# WORD_BYTE_1.net
KiCad netlist of a schematic drawn in EAGLE
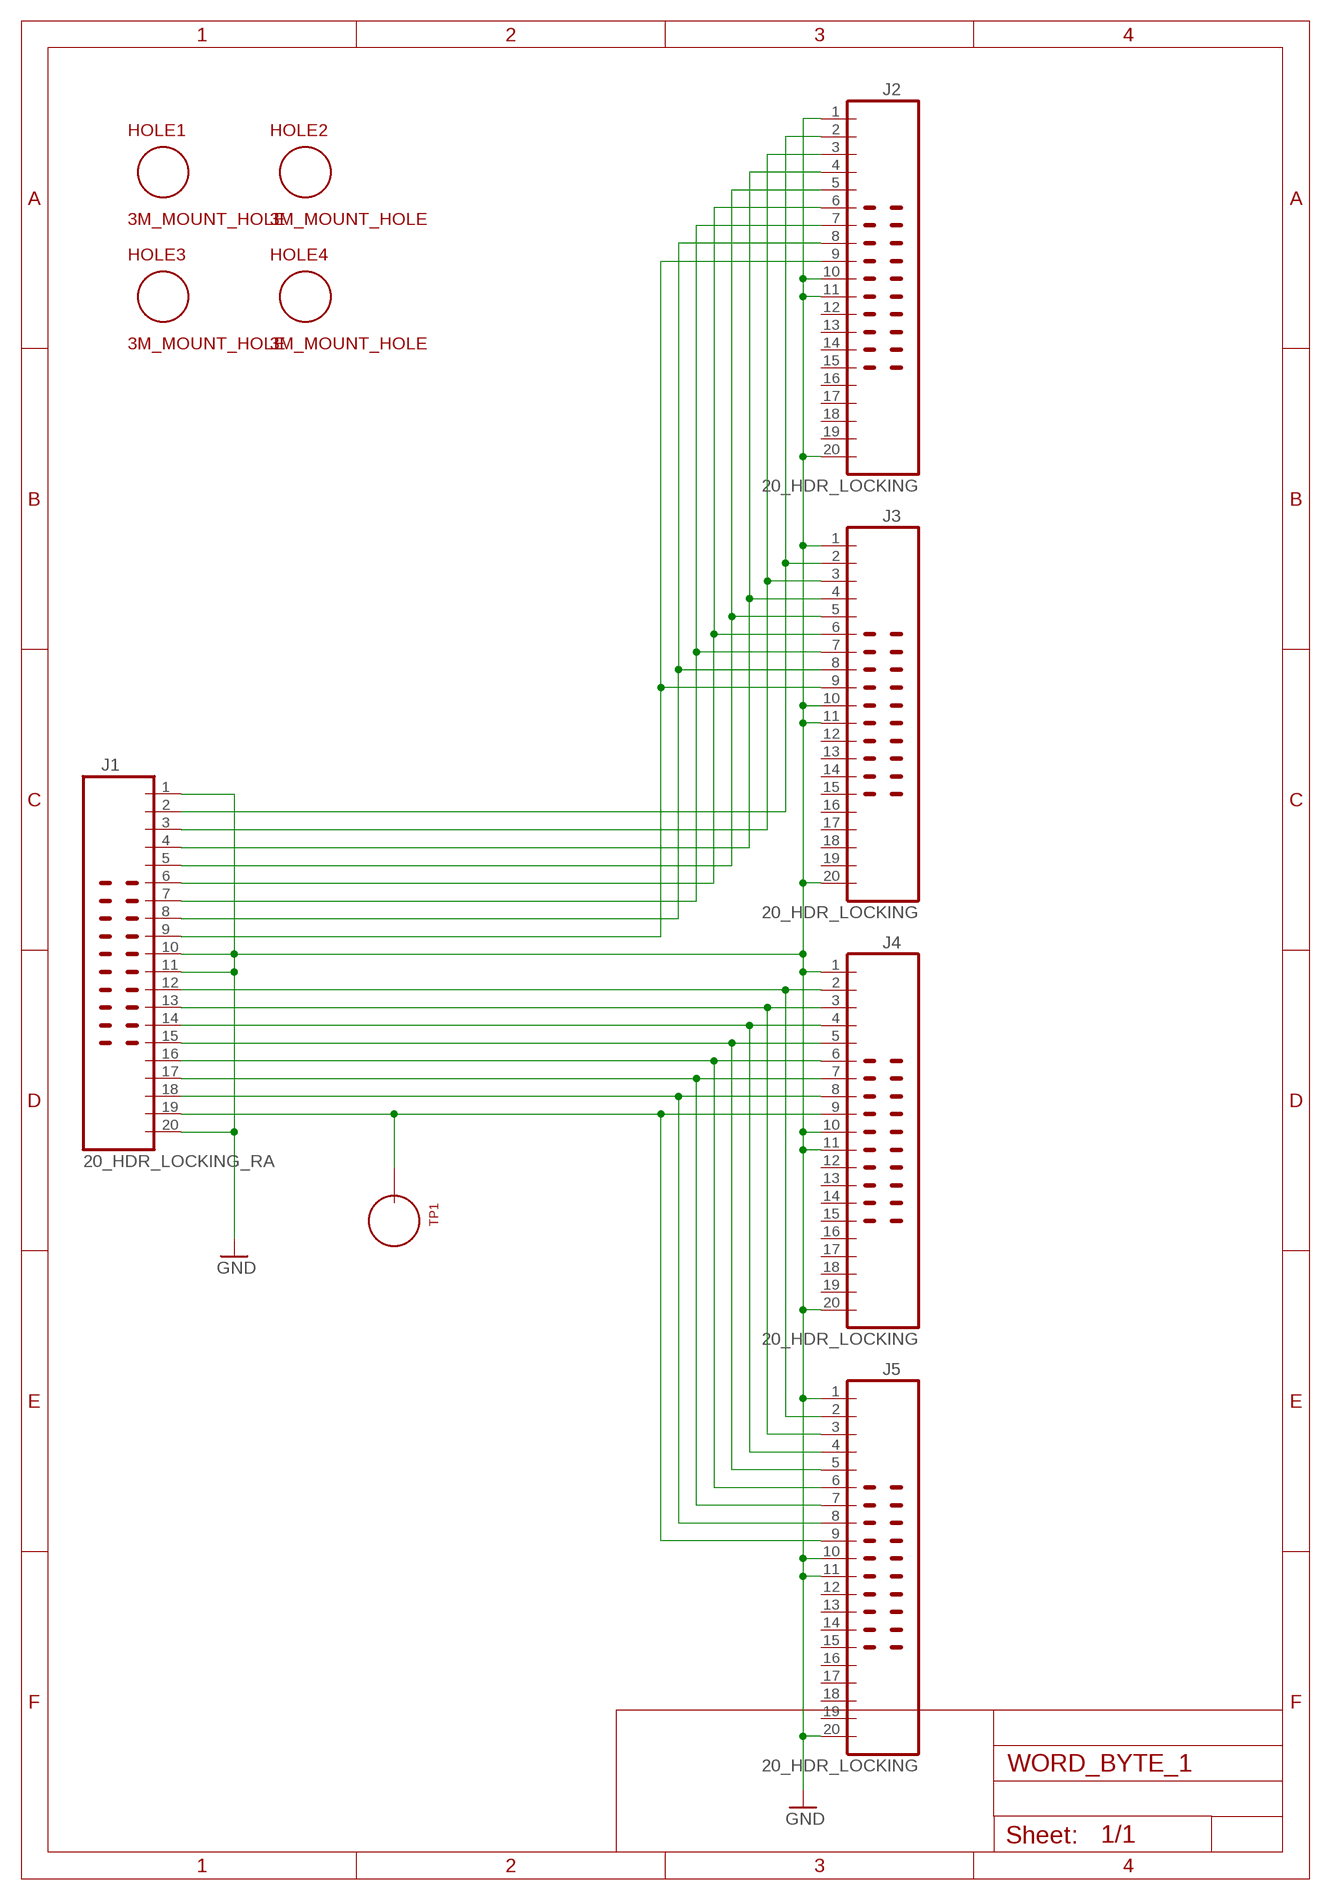
[diagram p0: schematic, sheet 1]

(export (version "E")
  (design (tool "Eeschema 10.0.6"))
  (components
    (comp (ref "HOLE1")
      (value "3M_MOUNT_HOLE")
      (footprint "eagle-import:3M_HOLE")
      (libsource (lib "eagle-import") (part "3M_MOUNT_HOLE"))
    )
    (comp (ref "HOLE2")
      (value "3M_MOUNT_HOLE")
      (footprint "eagle-import:3M_HOLE")
      (libsource (lib "eagle-import") (part "3M_MOUNT_HOLE"))
    )
    (comp (ref "HOLE3")
      (value "3M_MOUNT_HOLE")
      (footprint "eagle-import:3M_HOLE")
      (libsource (lib "eagle-import") (part "3M_MOUNT_HOLE"))
    )
    (comp (ref "HOLE4")
      (value "3M_MOUNT_HOLE")
      (footprint "eagle-import:3M_HOLE")
      (libsource (lib "eagle-import") (part "3M_MOUNT_HOLE"))
    )
    (comp (ref "J1")
      (value "20_HDR_LOCKING_RA")
      (footprint "eagle-import:20_HDR_LOCKING_RA")
      (libsource (lib "eagle-import") (part "20_HDR_LOCKING_RA"))
    )
    (comp (ref "J2")
      (value "20_HDR_LOCKING")
      (footprint "eagle-import:20_HDR_LOCKING")
      (libsource (lib "eagle-import") (part "20_HDR_LOCKING"))
    )
    (comp (ref "J3")
      (value "20_HDR_LOCKING")
      (footprint "eagle-import:20_HDR_LOCKING")
      (libsource (lib "eagle-import") (part "20_HDR_LOCKING"))
    )
    (comp (ref "J4")
      (value "20_HDR_LOCKING")
      (footprint "eagle-import:20_HDR_LOCKING")
      (libsource (lib "eagle-import") (part "20_HDR_LOCKING"))
    )
    (comp (ref "J5")
      (value "20_HDR_LOCKING")
      (footprint "eagle-import:20_HDR_LOCKING")
      (libsource (lib "eagle-import") (part "20_HDR_LOCKING"))
    )
    (comp (ref "TP1")
      (value "TEST_LOOP")
      (footprint "eagle-import:TEST_LOOP")
      (libsource (lib "eagle-import") (part "TEST_LOOP"))
    )
  )
  (nets
    (net (code "1") (name "GND") (class "Default")
      (node (ref "J1") (pin "1") (pinfunction "1_1") (pintype "bidirectional"))
      (node (ref "J1") (pin "10") (pinfunction "10_10") (pintype "bidirectional"))
      (node (ref "J1") (pin "11") (pinfunction "11_11") (pintype "bidirectional"))
      (node (ref "J1") (pin "20") (pinfunction "20_20") (pintype "bidirectional"))
      (node (ref "J2") (pin "1") (pinfunction "1_1") (pintype "bidirectional"))
      (node (ref "J2") (pin "10") (pinfunction "10_10") (pintype "bidirectional"))
      (node (ref "J2") (pin "11") (pinfunction "11_11") (pintype "bidirectional"))
      (node (ref "J2") (pin "20") (pinfunction "20_20") (pintype "bidirectional"))
      (node (ref "J3") (pin "1") (pinfunction "1_1") (pintype "bidirectional"))
      (node (ref "J3") (pin "10") (pinfunction "10_10") (pintype "bidirectional"))
      (node (ref "J3") (pin "11") (pinfunction "11_11") (pintype "bidirectional"))
      (node (ref "J3") (pin "20") (pinfunction "20_20") (pintype "bidirectional"))
      (node (ref "J4") (pin "1") (pinfunction "1_1") (pintype "bidirectional"))
      (node (ref "J4") (pin "10") (pinfunction "10_10") (pintype "bidirectional"))
      (node (ref "J4") (pin "11") (pinfunction "11_11") (pintype "bidirectional"))
      (node (ref "J4") (pin "20") (pinfunction "20_20") (pintype "bidirectional"))
      (node (ref "J5") (pin "1") (pinfunction "1_1") (pintype "bidirectional"))
      (node (ref "J5") (pin "10") (pinfunction "10_10") (pintype "bidirectional"))
      (node (ref "J5") (pin "11") (pinfunction "11_11") (pintype "bidirectional"))
      (node (ref "J5") (pin "20") (pinfunction "20_20") (pintype "bidirectional"))
    )
    (net (code "2") (name "Net-(J1-Pad2)") (class "Default")
      (node (ref "J1") (pin "2") (pinfunction "2_2") (pintype "bidirectional"))
      (node (ref "J2") (pin "2") (pinfunction "2_2") (pintype "bidirectional"))
      (node (ref "J3") (pin "2") (pinfunction "2_2") (pintype "bidirectional"))
    )
    (net (code "3") (name "Net-(J1-Pad3)") (class "Default")
      (node (ref "J1") (pin "3") (pinfunction "3_3") (pintype "bidirectional"))
      (node (ref "J2") (pin "3") (pinfunction "3_3") (pintype "bidirectional"))
      (node (ref "J3") (pin "3") (pinfunction "3_3") (pintype "bidirectional"))
    )
    (net (code "4") (name "Net-(J1-Pad4)") (class "Default")
      (node (ref "J1") (pin "4") (pinfunction "4_4") (pintype "bidirectional"))
      (node (ref "J2") (pin "4") (pinfunction "4_4") (pintype "bidirectional"))
      (node (ref "J3") (pin "4") (pinfunction "4_4") (pintype "bidirectional"))
    )
    (net (code "5") (name "Net-(J1-Pad5)") (class "Default")
      (node (ref "J1") (pin "5") (pinfunction "5_5") (pintype "bidirectional"))
      (node (ref "J2") (pin "5") (pinfunction "5_5") (pintype "bidirectional"))
      (node (ref "J3") (pin "5") (pinfunction "5_5") (pintype "bidirectional"))
    )
    (net (code "6") (name "Net-(J1-Pad6)") (class "Default")
      (node (ref "J1") (pin "6") (pinfunction "6_6") (pintype "bidirectional"))
      (node (ref "J2") (pin "6") (pinfunction "6_6") (pintype "bidirectional"))
      (node (ref "J3") (pin "6") (pinfunction "6_6") (pintype "bidirectional"))
    )
    (net (code "7") (name "Net-(J1-Pad7)") (class "Default")
      (node (ref "J1") (pin "7") (pinfunction "7_7") (pintype "bidirectional"))
      (node (ref "J2") (pin "7") (pinfunction "7_7") (pintype "bidirectional"))
      (node (ref "J3") (pin "7") (pinfunction "7_7") (pintype "bidirectional"))
    )
    (net (code "8") (name "Net-(J1-Pad8)") (class "Default")
      (node (ref "J1") (pin "8") (pinfunction "8_8") (pintype "bidirectional"))
      (node (ref "J2") (pin "8") (pinfunction "8_8") (pintype "bidirectional"))
      (node (ref "J3") (pin "8") (pinfunction "8_8") (pintype "bidirectional"))
    )
    (net (code "9") (name "Net-(J1-Pad9)") (class "Default")
      (node (ref "J1") (pin "9") (pinfunction "9_9") (pintype "bidirectional"))
      (node (ref "J2") (pin "9") (pinfunction "9_9") (pintype "bidirectional"))
      (node (ref "J3") (pin "9") (pinfunction "9_9") (pintype "bidirectional"))
    )
    (net (code "10") (name "Net-(J1-Pad12)") (class "Default")
      (node (ref "J1") (pin "12") (pinfunction "12_12") (pintype "bidirectional"))
      (node (ref "J4") (pin "2") (pinfunction "2_2") (pintype "bidirectional"))
      (node (ref "J5") (pin "2") (pinfunction "2_2") (pintype "bidirectional"))
    )
    (net (code "11") (name "Net-(J1-Pad13)") (class "Default")
      (node (ref "J1") (pin "13") (pinfunction "13_13") (pintype "bidirectional"))
      (node (ref "J4") (pin "3") (pinfunction "3_3") (pintype "bidirectional"))
      (node (ref "J5") (pin "3") (pinfunction "3_3") (pintype "bidirectional"))
    )
    (net (code "12") (name "Net-(J1-Pad14)") (class "Default")
      (node (ref "J1") (pin "14") (pinfunction "14_14") (pintype "bidirectional"))
      (node (ref "J4") (pin "4") (pinfunction "4_4") (pintype "bidirectional"))
      (node (ref "J5") (pin "4") (pinfunction "4_4") (pintype "bidirectional"))
    )
    (net (code "13") (name "Net-(J1-Pad15)") (class "Default")
      (node (ref "J1") (pin "15") (pinfunction "15_15") (pintype "bidirectional"))
      (node (ref "J4") (pin "5") (pinfunction "5_5") (pintype "bidirectional"))
      (node (ref "J5") (pin "5") (pinfunction "5_5") (pintype "bidirectional"))
    )
    (net (code "14") (name "Net-(J1-Pad16)") (class "Default")
      (node (ref "J1") (pin "16") (pinfunction "16_16") (pintype "bidirectional"))
      (node (ref "J4") (pin "6") (pinfunction "6_6") (pintype "bidirectional"))
      (node (ref "J5") (pin "6") (pinfunction "6_6") (pintype "bidirectional"))
    )
    (net (code "15") (name "Net-(J1-Pad17)") (class "Default")
      (node (ref "J1") (pin "17") (pinfunction "17_17") (pintype "bidirectional"))
      (node (ref "J4") (pin "7") (pinfunction "7_7") (pintype "bidirectional"))
      (node (ref "J5") (pin "7") (pinfunction "7_7") (pintype "bidirectional"))
    )
    (net (code "16") (name "Net-(J1-Pad18)") (class "Default")
      (node (ref "J1") (pin "18") (pinfunction "18_18") (pintype "bidirectional"))
      (node (ref "J4") (pin "8") (pinfunction "8_8") (pintype "bidirectional"))
      (node (ref "J5") (pin "8") (pinfunction "8_8") (pintype "bidirectional"))
    )
    (net (code "17") (name "Net-(J1-Pad19)") (class "Default")
      (node (ref "J1") (pin "19") (pinfunction "19_19") (pintype "bidirectional"))
      (node (ref "J4") (pin "9") (pinfunction "9_9") (pintype "bidirectional"))
      (node (ref "J5") (pin "9") (pinfunction "9_9") (pintype "bidirectional"))
      (node (ref "TP1") (pin "P$1") (pinfunction "P$1_P$1") (pintype "bidirectional"))
    )
    (net (code "18") (name "unconnected-(J2-Pad12)") (class "Default")
      (node (ref "J2") (pin "12") (pinfunction "12_12") (pintype "bidirectional"))
    )
    (net (code "19") (name "unconnected-(J2-Pad13)") (class "Default")
      (node (ref "J2") (pin "13") (pinfunction "13_13") (pintype "bidirectional"))
    )
    (net (code "20") (name "unconnected-(J2-Pad14)") (class "Default")
      (node (ref "J2") (pin "14") (pinfunction "14_14") (pintype "bidirectional"))
    )
    (net (code "21") (name "unconnected-(J2-Pad15)") (class "Default")
      (node (ref "J2") (pin "15") (pinfunction "15_15") (pintype "bidirectional"))
    )
    (net (code "22") (name "unconnected-(J2-Pad16)") (class "Default")
      (node (ref "J2") (pin "16") (pinfunction "16_16") (pintype "bidirectional"))
    )
    (net (code "23") (name "unconnected-(J2-Pad17)") (class "Default")
      (node (ref "J2") (pin "17") (pinfunction "17_17") (pintype "bidirectional"))
    )
    (net (code "24") (name "unconnected-(J2-Pad18)") (class "Default")
      (node (ref "J2") (pin "18") (pinfunction "18_18") (pintype "bidirectional"))
    )
    (net (code "25") (name "unconnected-(J2-Pad19)") (class "Default")
      (node (ref "J2") (pin "19") (pinfunction "19_19") (pintype "bidirectional"))
    )
    (net (code "26") (name "unconnected-(J3-Pad12)") (class "Default")
      (node (ref "J3") (pin "12") (pinfunction "12_12") (pintype "bidirectional"))
    )
    (net (code "27") (name "unconnected-(J3-Pad13)") (class "Default")
      (node (ref "J3") (pin "13") (pinfunction "13_13") (pintype "bidirectional"))
    )
    (net (code "28") (name "unconnected-(J3-Pad14)") (class "Default")
      (node (ref "J3") (pin "14") (pinfunction "14_14") (pintype "bidirectional"))
    )
    (net (code "29") (name "unconnected-(J3-Pad15)") (class "Default")
      (node (ref "J3") (pin "15") (pinfunction "15_15") (pintype "bidirectional"))
    )
    (net (code "30") (name "unconnected-(J3-Pad16)") (class "Default")
      (node (ref "J3") (pin "16") (pinfunction "16_16") (pintype "bidirectional"))
    )
    (net (code "31") (name "unconnected-(J3-Pad17)") (class "Default")
      (node (ref "J3") (pin "17") (pinfunction "17_17") (pintype "bidirectional"))
    )
    (net (code "32") (name "unconnected-(J3-Pad18)") (class "Default")
      (node (ref "J3") (pin "18") (pinfunction "18_18") (pintype "bidirectional"))
    )
    (net (code "33") (name "unconnected-(J3-Pad19)") (class "Default")
      (node (ref "J3") (pin "19") (pinfunction "19_19") (pintype "bidirectional"))
    )
    (net (code "34") (name "unconnected-(J4-Pad12)") (class "Default")
      (node (ref "J4") (pin "12") (pinfunction "12_12") (pintype "bidirectional"))
    )
    (net (code "35") (name "unconnected-(J4-Pad13)") (class "Default")
      (node (ref "J4") (pin "13") (pinfunction "13_13") (pintype "bidirectional"))
    )
    (net (code "36") (name "unconnected-(J4-Pad14)") (class "Default")
      (node (ref "J4") (pin "14") (pinfunction "14_14") (pintype "bidirectional"))
    )
    (net (code "37") (name "unconnected-(J4-Pad15)") (class "Default")
      (node (ref "J4") (pin "15") (pinfunction "15_15") (pintype "bidirectional"))
    )
    (net (code "38") (name "unconnected-(J4-Pad16)") (class "Default")
      (node (ref "J4") (pin "16") (pinfunction "16_16") (pintype "bidirectional"))
    )
    (net (code "39") (name "unconnected-(J4-Pad17)") (class "Default")
      (node (ref "J4") (pin "17") (pinfunction "17_17") (pintype "bidirectional"))
    )
    (net (code "40") (name "unconnected-(J4-Pad18)") (class "Default")
      (node (ref "J4") (pin "18") (pinfunction "18_18") (pintype "bidirectional"))
    )
    (net (code "41") (name "unconnected-(J4-Pad19)") (class "Default")
      (node (ref "J4") (pin "19") (pinfunction "19_19") (pintype "bidirectional"))
    )
    (net (code "42") (name "unconnected-(J5-Pad12)") (class "Default")
      (node (ref "J5") (pin "12") (pinfunction "12_12") (pintype "bidirectional"))
    )
    (net (code "43") (name "unconnected-(J5-Pad13)") (class "Default")
      (node (ref "J5") (pin "13") (pinfunction "13_13") (pintype "bidirectional"))
    )
    (net (code "44") (name "unconnected-(J5-Pad14)") (class "Default")
      (node (ref "J5") (pin "14") (pinfunction "14_14") (pintype "bidirectional"))
    )
    (net (code "45") (name "unconnected-(J5-Pad15)") (class "Default")
      (node (ref "J5") (pin "15") (pinfunction "15_15") (pintype "bidirectional"))
    )
    (net (code "46") (name "unconnected-(J5-Pad16)") (class "Default")
      (node (ref "J5") (pin "16") (pinfunction "16_16") (pintype "bidirectional"))
    )
    (net (code "47") (name "unconnected-(J5-Pad17)") (class "Default")
      (node (ref "J5") (pin "17") (pinfunction "17_17") (pintype "bidirectional"))
    )
    (net (code "48") (name "unconnected-(J5-Pad18)") (class "Default")
      (node (ref "J5") (pin "18") (pinfunction "18_18") (pintype "bidirectional"))
    )
    (net (code "49") (name "unconnected-(J5-Pad19)") (class "Default")
      (node (ref "J5") (pin "19") (pinfunction "19_19") (pintype "bidirectional"))
    )
  )
)
